# highVoltage.net
KiCad netlist of a schematic drawn in Altium Designer
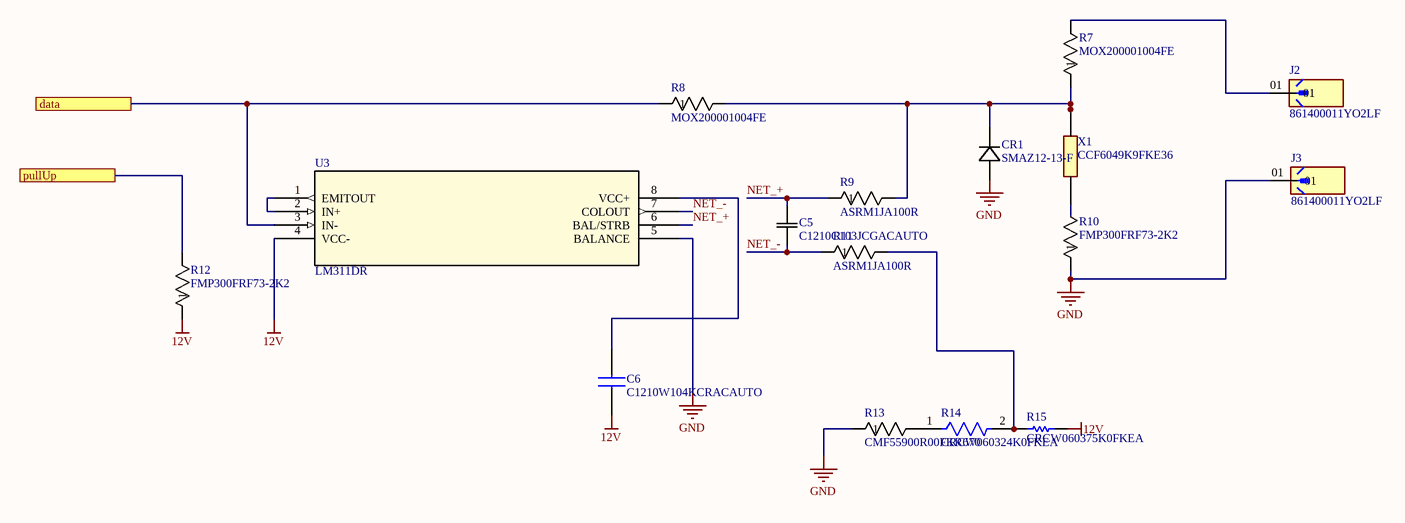
[diagram p0: highVoltage.SchDoc]

(export (version "E")
  (design (tool "Eeschema 10.0.6"))
  (components
    (comp (ref "C5")
      (value "C1210C103JCGACAUTO")
      (footprint "CAPC340270_140N_KEM")
      (description "No Description Available")
      (fields (field (name "COPYRIGHT") "Copyright (C) 2024 Ultra Librarian. All rights reserved."))
      (libsource (lib "C1210C103JCGACAUTO") (part "C1210C103JCGACAUTO"))
    )
    (comp (ref "C6")
      (value "C1210W104KCRACAUTO")
      (footprint "CAPC3225X230N")
      (fields (field (name "MOUSER PART NUMBER") "80-C1210W104KCRAUTO"))
      (libsource (lib "C1210W104KCRACAUTO") (part "C1210W104KCRACAUTO"))
    )
    (comp (ref "CR1")
      (value "SMAZ12-13-F")
      (footprint "SMAZ12-13-F:SMA_DIO")
      (description "No Description Available")
      (fields (field (name "COPYRIGHT") "Copyright (C) 2024 Ultra Librarian. All rights reserved."))
      (libsource (lib "SMAZ12-13-F") (part "SMAZ12-13-F"))
    )
    (comp (ref "J2")
      (value "861400011YO2LF")
      (footprint "AMPHENOL_861400011YO2LF")
      (description "Board to Board connector, Unshrouded Header, Through Hole, Single Row, 1 Position, Vertical.")
      (fields
        (field (name "DIGI-KEY_PART_NUMBER") "609-861400011YO2LF-ND")
        (field (name "MF") "AMPHENOL ICC / FCI")
      )
      (libsource (lib "861400011YO2LF") (part "861400011YO2LF"))
    )
    (comp (ref "J3")
      (value "861400011YO2LF")
      (footprint "AMPHENOL_861400011YO2LF")
      (description "Board to Board connector, Unshrouded Header, Through Hole, Single Row, 1 Position, Vertical.")
      (fields
        (field (name "DIGI-KEY_PART_NUMBER") "609-861400011YO2LF-ND")
        (field (name "MF") "AMPHENOL ICC / FCI")
      )
      (libsource (lib "861400011YO2LF") (part "861400011YO2LF"))
    )
    (comp (ref "R7")
      (value "MOX200001004FE")
      (footprint "RES_MOX-200_OHM")
      (description "No Description Available")
      (fields (field (name "COPYRIGHT") "Copyright (C) 2024 Ultra Librarian. All rights reserved."))
      (libsource (lib "MOX200001004FE") (part "MOX200001004FE"))
    )
    (comp (ref "R8")
      (value "MOX200001004FE")
      (footprint "RES_MOX-200_OHM")
      (description "No Description Available")
      (fields (field (name "COPYRIGHT") "Copyright (C) 2024 Ultra Librarian. All rights reserved."))
      (libsource (lib "MOX200001004FE") (part "MOX200001004FE"))
    )
    (comp (ref "R9")
      (value "ASRM1JA100R")
      (footprint "RES_ASRM1_STP")
      (description "No Description Available")
      (fields (field (name "COPYRIGHT") "Copyright (C) 2024 Ultra Librarian. All rights reserved."))
      (libsource (lib "ASRM1JA100R") (part "ASRM1JA100R"))
    )
    (comp (ref "R10")
      (value "FMP300FRF73-2K2")
      (footprint "RES_FMP300_15P5X5_YAG")
      (description "No Description Available")
      (fields (field (name "COPYRIGHT") "Copyright (C) 2024 Ultra Librarian. All rights reserved."))
      (libsource (lib "FMP300FRF73-2K2") (part "FMP300FRF73-2K2"))
    )
    (comp (ref "R11")
      (value "ASRM1JA100R")
      (footprint "RES_ASRM1_STP")
      (description "No Description Available")
      (fields (field (name "COPYRIGHT") "Copyright (C) 2024 Ultra Librarian. All rights reserved."))
      (libsource (lib "ASRM1JA100R") (part "ASRM1JA100R"))
    )
    (comp (ref "R12")
      (value "FMP300FRF73-2K2")
      (footprint "RES_FMP300_15P5X5_YAG")
      (description "No Description Available")
      (fields (field (name "COPYRIGHT") "Copyright (C) 2024 Ultra Librarian. All rights reserved."))
      (libsource (lib "FMP300FRF73-2K2") (part "FMP300FRF73-2K2"))
    )
    (comp (ref "R13")
      (value "CMF55900R00FKR670")
      (footprint "RES_CMF07_VIS")
      (description "No Description Available")
      (fields (field (name "COPYRIGHT") "Copyright (C) 2024 Ultra Librarian. All rights reserved."))
      (libsource (lib "CMF55900R00FKR670") (part "CMF55900R00FKR670"))
    )
    (comp (ref "R14")
      (value "CRCW060324K0FKEA")
      (footprint "FP-CRCW0603-e3-IPC_C")
      (description "RES Thick Film, 24kΩ, 1%, 0.1W, 100ppm/°C, 0603")
      (fields (field (name "TOLERANCE") "1%"))
      (libsource (lib "Altium Content Vault") (part "1029c3af85768c4190bb7ad29bc67b5"))
    )
    (comp (ref "R15")
      (value "CRCW060375K0FKEA")
      (footprint "RESC1609X50X30NL10T20")
      (fields (field (name "MANUFACTURER") "Vishay Dale"))
      (libsource (lib "Altium Content Vault") (part "RES"))
    )
    (comp (ref "U3")
      (value "LM311DR")
      (footprint "D8")
      (description "No Description Available")
      (fields (field (name "COPYRIGHT") "Copyright (C) 2024 Ultra Librarian. All rights reserved."))
      (libsource (lib "LM311DR") (part "LM311DR"))
    )
    (comp (ref "X1")
      (value "CCF6049K9FKE36")
      (footprint "RESAD2428W69L1016D353")
      (description "Metal Film Resistors - Through Hole 1/2watt 49.9Kohms 1% Rated to 1watt")
      (libsource (lib "CCF6049K9FKE36") (part "CCF6049K9FKE36"))
    )
  )
  (nets
    (net (code "1") (name "/NET_+") (class "Default")
      (node (ref "C5") (pin "2") (pinfunction "2_2") (pintype "passive"))
      (node (ref "R9") (pin "1") (pinfunction "1_1") (pintype "passive"))
      (node (ref "U3") (pin "6") (pinfunction "BAL/STRB_6") (pintype "passive"))
    )
    (net (code "2") (name "/NET_-") (class "Default")
      (node (ref "C5") (pin "1") (pinfunction "1_1") (pintype "passive"))
      (node (ref "R11") (pin "1") (pinfunction "1_1") (pintype "passive"))
      (node (ref "U3") (pin "7") (pinfunction "COLOUT_7") (pintype "output"))
    )
    (net (code "3") (name "/data") (class "Default")
      (node (ref "R8") (pin "1") (pinfunction "1_1") (pintype "passive"))
      (node (ref "U3") (pin "3") (pinfunction "IN-_3") (pintype "input"))
    )
    (net (code "4") (name "/pullUp") (class "Default")
      (node (ref "R12") (pin "2") (pinfunction "2_2") (pintype "passive"))
    )
    (net (code "5") (name "12V") (class "Default")
      (node (ref "C6") (pin "1") (pinfunction "1_1") (pintype "passive"))
      (node (ref "R12") (pin "1") (pinfunction "1_1") (pintype "passive"))
      (node (ref "R15") (pin "2") (pinfunction "2_2") (pintype "passive"))
      (node (ref "U3") (pin "4") (pinfunction "VCC-_4") (pintype "power_in"))
    )
    (net (code "6") (name "GND") (class "Default")
      (node (ref "J3") (pin "01") (pinfunction "01_01") (pintype "passive"))
      (node (ref "R10") (pin "1") (pinfunction "1_1") (pintype "passive"))
      (node (ref "R13") (pin "1") (pinfunction "1_1") (pintype "passive"))
      (node (ref "U3") (pin "5") (pinfunction "BALANCE_5") (pintype "passive"))
    )
    (net (code "7") (name "Net-(CR1-Pad1)") (class "Default")
      (node (ref "CR1") (pin "1") (pinfunction "1_1") (pintype "passive"))
      (node (ref "R7") (pin "1") (pinfunction "1_1") (pintype "passive"))
      (node (ref "R8") (pin "2") (pinfunction "2_2") (pintype "passive"))
      (node (ref "R9") (pin "2") (pinfunction "2_2") (pintype "passive"))
      (node (ref "X1") (pin "2") (pinfunction "2_2") (pintype "passive"))
    )
    (net (code "8") (name "Net-(J2-Pad01)") (class "Default")
      (node (ref "J2") (pin "01") (pinfunction "01_01") (pintype "passive"))
      (node (ref "R7") (pin "2") (pinfunction "2_2") (pintype "passive"))
    )
    (net (code "9") (name "Net-(R10-Pad2)") (class "Default")
      (node (ref "R10") (pin "2") (pinfunction "2_2") (pintype "passive"))
      (node (ref "X1") (pin "1") (pinfunction "1_1") (pintype "passive"))
    )
    (net (code "10") (name "Net-(R11-Pad2)") (class "Default")
      (node (ref "R11") (pin "2") (pinfunction "2_2") (pintype "passive"))
      (node (ref "R14") (pin "2") (pinfunction "2_2") (pintype "passive"))
      (node (ref "R15") (pin "1") (pinfunction "1_1") (pintype "passive"))
    )
    (net (code "11") (name "Net-(R13-Pad2)") (class "Default")
      (node (ref "R13") (pin "2") (pinfunction "2_2") (pintype "passive"))
      (node (ref "R14") (pin "1") (pinfunction "1_1") (pintype "passive"))
    )
    (net (code "12") (name "Net-(U3-EMITOUT)") (class "Default")
      (node (ref "U3") (pin "1") (pinfunction "EMITOUT_1") (pintype "output"))
      (node (ref "U3") (pin "2") (pinfunction "IN+_2") (pintype "input"))
    )
    (net (code "13") (name "Net-(U3-VCC+)") (class "Default")
      (node (ref "C6") (pin "2") (pinfunction "2_2") (pintype "passive"))
      (node (ref "U3") (pin "8") (pinfunction "VCC+_8") (pintype "power_in"))
    )
    (net (code "14") (name "unconnected-(CR1-Pad2)") (class "Default")
      (node (ref "CR1") (pin "2") (pinfunction "2_2") (pintype "passive"))
    )
  )
)
